# ScannerV2.net
KiCad netlist of a schematic drawn in Altium Designer
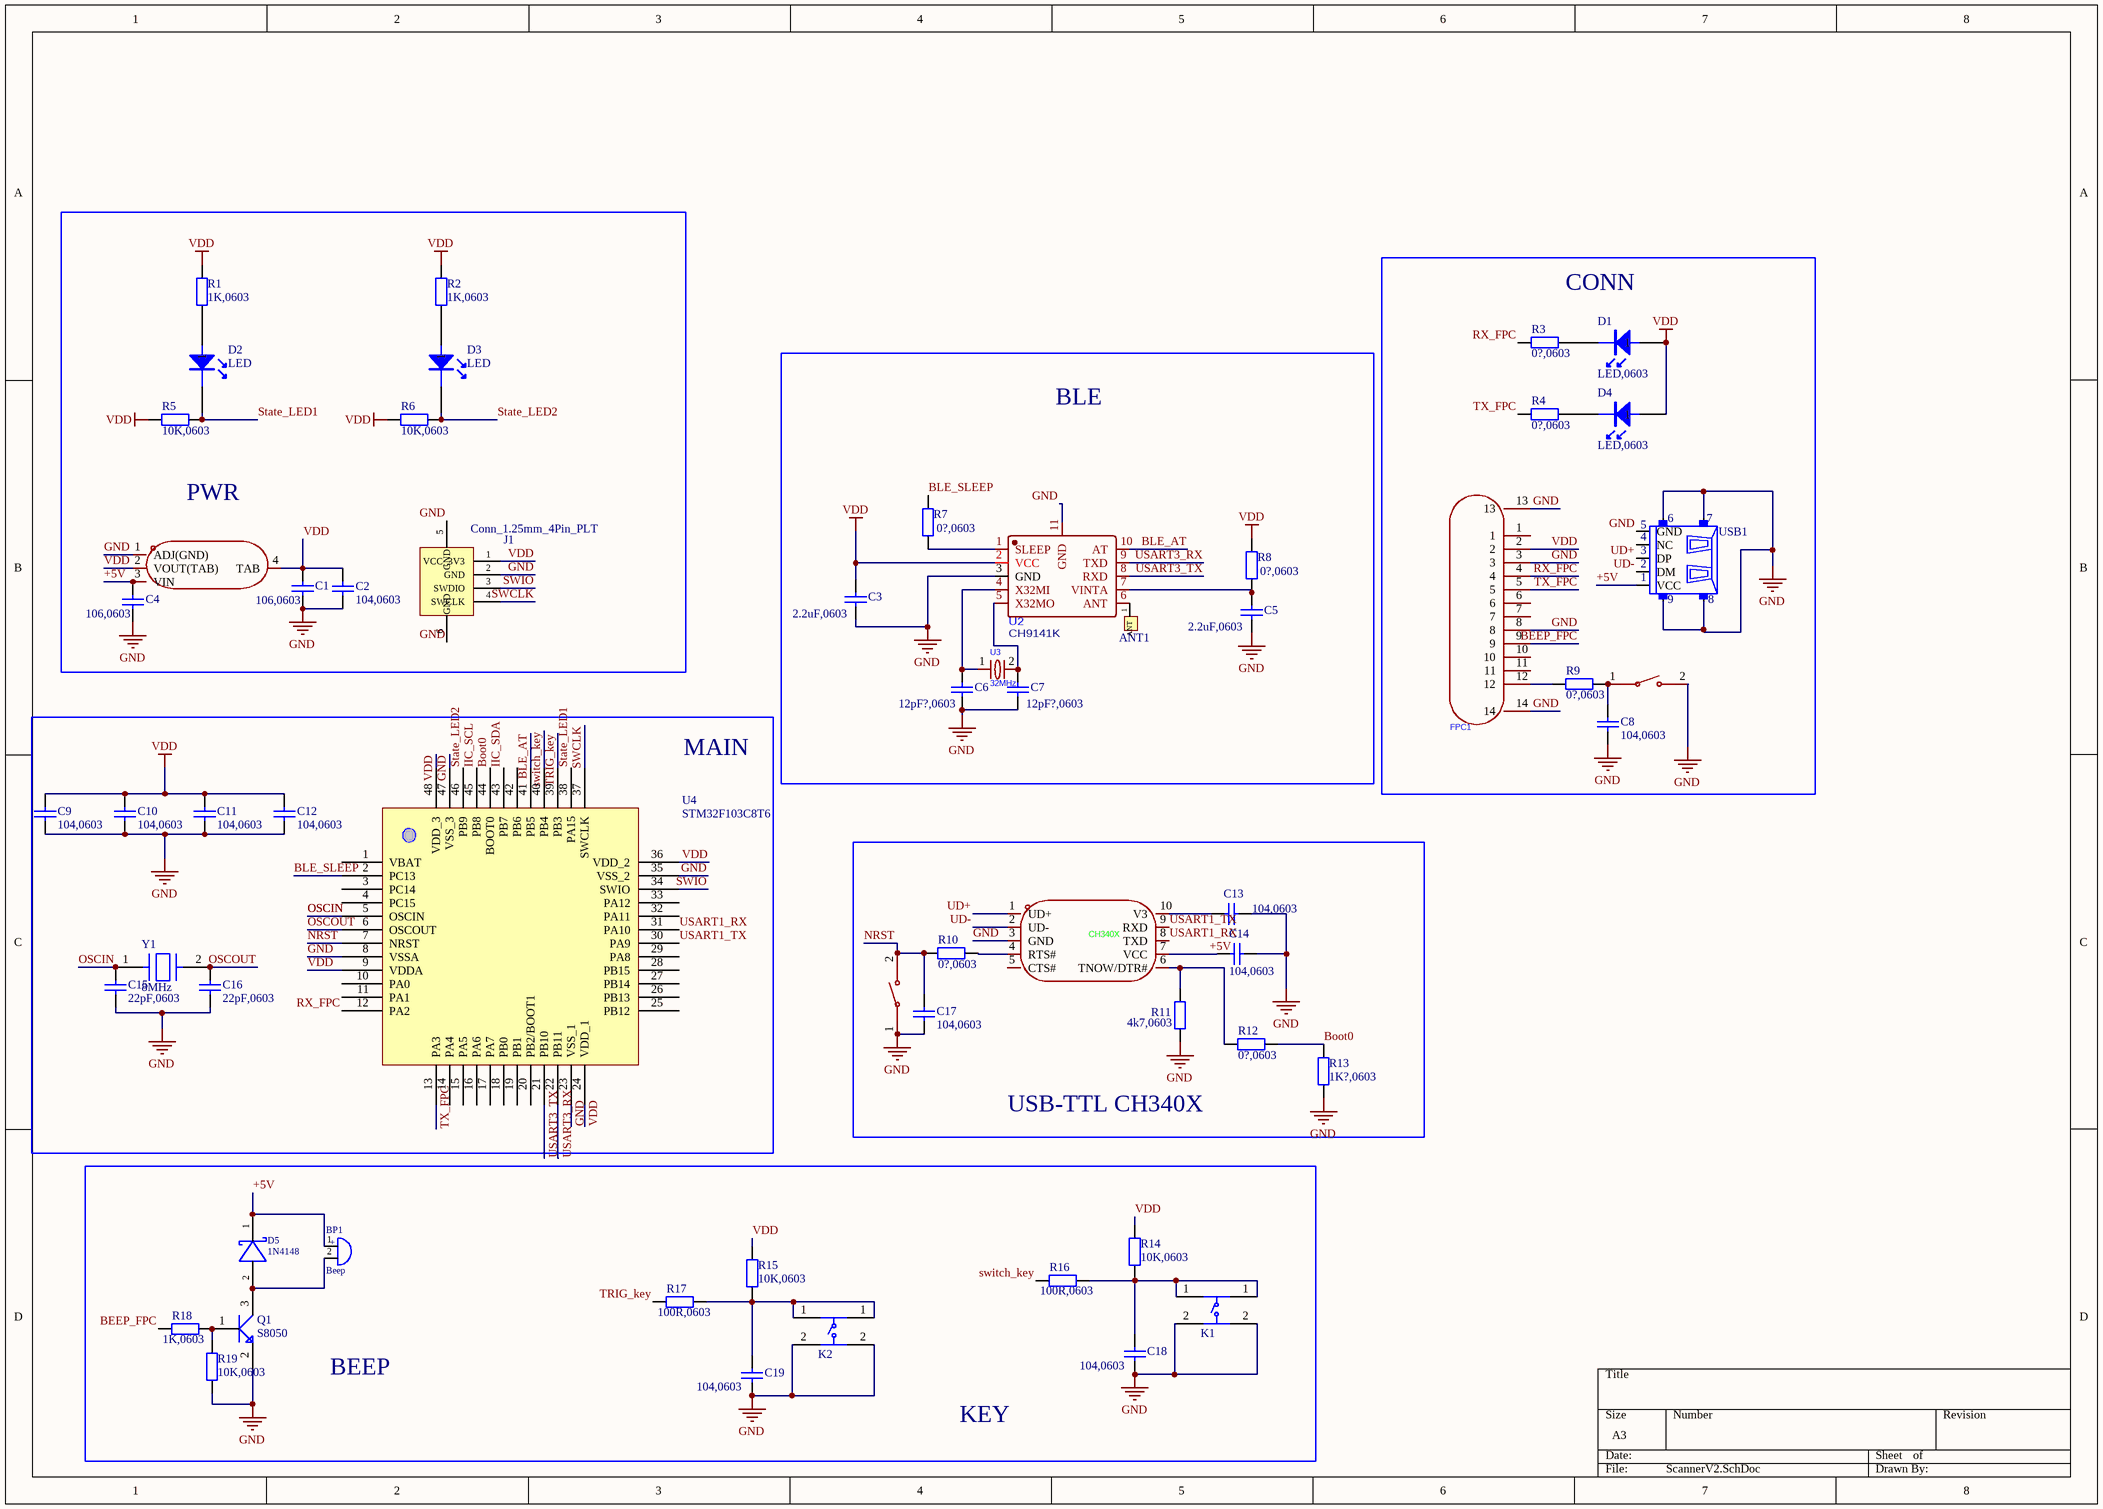
[diagram p0: ScannerV2.SchDoc]

(export (version "E")
  (design (tool "Eeschema 10.0.6"))
  (components
    (comp (ref "ANT1") (value "ANT") (footprint "IPX-2.0") (libsource (lib "HyperSTD") (part "ANT_IPX")))
    (comp (ref "BP1") (value "Beep") (footprint "BEEP") (libsource (lib "MQTT_SelService_V1") (part "Beep")))
    (comp (ref "C1")
      (value "106,0603")
      (footprint "C0603")
      (description "105,0603")
      (fields (field (name "PUBLISHER") "Altium Limited"))
      (libsource (lib "MQTT_SelService_V1") (part "Cap2"))
    )
    (comp (ref "C2")
      (value "104,0603")
      (footprint "C0603")
      (description "105,0603")
      (fields (field (name "PUBLISHER") "Altium Limited"))
      (libsource (lib "MQTT_SelService_V1") (part "Cap2"))
    )
    (comp (ref "C3")
      (value "2.2uF,0603")
      (footprint "C0603")
      (description "105,0603")
      (fields (field (name "PUBLISHER") "Altium Limited"))
      (libsource (lib "MQTT_SelService_V1") (part "Cap2"))
    )
    (comp (ref "C4")
      (value "106,0603")
      (footprint "C0603")
      (description "105,0603")
      (fields (field (name "PUBLISHER") "Altium Limited"))
      (libsource (lib "MQTT_SelService_V1") (part "Cap2"))
    )
    (comp (ref "C5")
      (value "2.2uF,0603")
      (footprint "C0603")
      (description "105,0603")
      (fields (field (name "PUBLISHER") "Altium Limited"))
      (libsource (lib "MQTT_SelService_V1") (part "Cap2"))
    )
    (comp (ref "C6")
      (value "12pF?,0603")
      (footprint "C0603")
      (description "105,0603")
      (fields (field (name "PUBLISHER") "Altium Limited"))
      (libsource (lib "MQTT_SelService_V1") (part "Cap2"))
    )
    (comp (ref "C7")
      (value "12pF?,0603")
      (footprint "C0603")
      (description "105,0603")
      (fields (field (name "PUBLISHER") "Altium Limited"))
      (libsource (lib "MQTT_SelService_V1") (part "Cap2"))
    )
    (comp (ref "C8")
      (value "104,0603")
      (footprint "C0603")
      (description "105,0603")
      (fields (field (name "PUBLISHER") "Altium Limited"))
      (libsource (lib "MQTT_SelService_V1") (part "Cap2"))
    )
    (comp (ref "C9")
      (value "104,0603")
      (footprint "C0603")
      (description "105,0603")
      (fields (field (name "PUBLISHER") "Altium Limited"))
      (libsource (lib "MQTT_SelService_V1") (part "Cap2"))
    )
    (comp (ref "C10")
      (value "104,0603")
      (footprint "C0603")
      (description "105,0603")
      (fields (field (name "PUBLISHER") "Altium Limited"))
      (libsource (lib "MQTT_SelService_V1") (part "Cap2"))
    )
    (comp (ref "C11")
      (value "104,0603")
      (footprint "C0603")
      (description "105,0603")
      (fields (field (name "PUBLISHER") "Altium Limited"))
      (libsource (lib "MQTT_SelService_V1") (part "Cap2"))
    )
    (comp (ref "C12")
      (value "104,0603")
      (footprint "C0603")
      (description "105,0603")
      (fields (field (name "PUBLISHER") "Altium Limited"))
      (libsource (lib "MQTT_SelService_V1") (part "Cap2"))
    )
    (comp (ref "C13")
      (value "104,0603")
      (footprint "C0603")
      (description "105,0603")
      (fields (field (name "PUBLISHER") "Altium Limited"))
      (libsource (lib "MQTT_SelService_V1") (part "Cap2"))
    )
    (comp (ref "C14")
      (value "104,0603")
      (footprint "C0603")
      (description "105,0603")
      (fields (field (name "PUBLISHER") "Altium Limited"))
      (libsource (lib "MQTT_SelService_V1") (part "Cap2"))
    )
    (comp (ref "C15")
      (value "22pF,0603")
      (footprint "C0603")
      (description "105,0603")
      (fields (field (name "PUBLISHER") "Altium Limited"))
      (libsource (lib "MQTT_SelService_V1") (part "Cap2"))
    )
    (comp (ref "C16")
      (value "22pF,0603")
      (footprint "C0603")
      (description "105,0603")
      (fields (field (name "PUBLISHER") "Altium Limited"))
      (libsource (lib "MQTT_SelService_V1") (part "Cap2"))
    )
    (comp (ref "C17")
      (value "104,0603")
      (footprint "C0603")
      (description "105,0603")
      (fields (field (name "PUBLISHER") "Altium Limited"))
      (libsource (lib "MQTT_SelService_V1") (part "Cap2"))
    )
    (comp (ref "C18")
      (value "104,0603")
      (footprint "C0603")
      (description "105,0603")
      (fields (field (name "PUBLISHER") "Altium Limited"))
      (libsource (lib "MQTT_SelService_V1") (part "Cap2"))
    )
    (comp (ref "C19")
      (value "104,0603")
      (footprint "C0603")
      (description "105,0603")
      (fields (field (name "PUBLISHER") "Altium Limited"))
      (libsource (lib "MQTT_SelService_V1") (part "Cap2"))
    )
    (comp (ref "D1")
      (value "LED,0603")
      (footprint "LED0603")
      (libsource (lib "MQTT_SelService_V1") (part "LED0603"))
    )
    (comp (ref "D2")
      (value "LED")
      (footprint "LED-2.5mm")
      (libsource (lib "MQTT_SelService_V1") (part "LED"))
    )
    (comp (ref "D3")
      (value "LED")
      (footprint "LED-2.5mm")
      (libsource (lib "MQTT_SelService_V1") (part "LED"))
    )
    (comp (ref "D4")
      (value "LED,0603")
      (footprint "LED0603")
      (libsource (lib "MQTT_SelService_V1") (part "LED0603"))
    )
    (comp (ref "D5")
      (value "1N4148")
      (footprint "1N4148")
      (description "SOD-123")
      (libsource (lib "MQTT_SelService_V1") (part "1N4148"))
    )
    (comp (ref "FPC1")
      (value "AFC01-S12FCA-00")
      (footprint "CONN-SMD-12P_AFC11-S12ICA-00")
      (fields (field (name "MANUFACTURER") "JS(钜硕电子)"))
      (libsource (lib "MQTT_SelService_V1") (part "FPC-12Pin_0.5"))
    )
    (comp (ref "J1")
      (value "Conn_1.25mm_4Pin_PLT")
      (footprint "CONN-SMD_4P-P1.25_HCTL_HC-1.25-4PLT")
      (description "SWD_Conn")
      (libsource (lib "MQTT_SelService_V1") (part "Conn_1.25mm_4Pin_PLT"))
    )
    (comp (ref "K1")
      (value "TS665CJ")
      (footprint "KEY12*12")
      (description "矩阵按键")
      (libsource (lib "MQTT_SelService_V1") (part "TS665CJ"))
    )
    (comp (ref "K2")
      (value "TS665CJ")
      (footprint "KEY12*12")
      (description "矩阵按键")
      (libsource (lib "MQTT_SelService_V1") (part "TS665CJ"))
    )
    (comp (ref "Q1")
      (value "S8050")
      (footprint "S8050")
      (libsource (lib "MQTT_SelService_V1") (part "S8050"))
    )
    (comp (ref "R1")
      (value "1K,0603")
      (footprint "R0603")
      (description "0603")
      (fields (field (name "PUBLISHER") "Altium Limited"))
      (libsource (lib "") (part "Res2_1"))
    )
    (comp (ref "R2")
      (value "1K,0603")
      (footprint "R0603")
      (description "0603")
      (fields (field (name "PUBLISHER") "Altium Limited"))
      (libsource (lib "") (part "Res2_1"))
    )
    (comp (ref "R3")
      (value "0?,0603")
      (footprint "R0603")
      (description "0603")
      (fields (field (name "PUBLISHER") "Altium Limited"))
      (libsource (lib "MQTT_SelService_V1") (part "Res2"))
    )
    (comp (ref "R4")
      (value "0?,0603")
      (footprint "R0603")
      (description "0603")
      (fields (field (name "PUBLISHER") "Altium Limited"))
      (libsource (lib "MQTT_SelService_V1") (part "Res2"))
    )
    (comp (ref "R5")
      (value "10K,0603")
      (footprint "R0603")
      (description "0603")
      (fields (field (name "PUBLISHER") "Altium Limited"))
      (libsource (lib "MQTT_SelService_V1") (part "Res2"))
    )
    (comp (ref "R6")
      (value "10K,0603")
      (footprint "R0603")
      (description "0603")
      (fields (field (name "PUBLISHER") "Altium Limited"))
      (libsource (lib "MQTT_SelService_V1") (part "Res2"))
    )
    (comp (ref "R7")
      (value "0?,0603")
      (footprint "R0603")
      (description "0603")
      (fields (field (name "PUBLISHER") "Altium Limited"))
      (libsource (lib "") (part "Res2_1"))
    )
    (comp (ref "R8")
      (value "0?,0603")
      (footprint "R0603")
      (description "0603")
      (fields (field (name "PUBLISHER") "Altium Limited"))
      (libsource (lib "") (part "Res2_1"))
    )
    (comp (ref "R9")
      (value "0?,0603")
      (footprint "R0603")
      (description "0603")
      (fields (field (name "PUBLISHER") "Altium Limited"))
      (libsource (lib "MQTT_SelService_V1") (part "Res2"))
    )
    (comp (ref "R10")
      (value "0?,0603")
      (footprint "R0603")
      (description "0603")
      (fields (field (name "PUBLISHER") "Altium Limited"))
      (libsource (lib "MQTT_SelService_V1") (part "Res2"))
    )
    (comp (ref "R11")
      (value "4k7,0603")
      (footprint "R0603")
      (description "0603")
      (fields (field (name "PUBLISHER") "Altium Limited"))
      (libsource (lib "") (part "Res2_3"))
    )
    (comp (ref "R12")
      (value "0?,0603")
      (footprint "R0603")
      (description "0603")
      (fields (field (name "PUBLISHER") "Altium Limited"))
      (libsource (lib "MQTT_SelService_V1") (part "Res2"))
    )
    (comp (ref "R13")
      (value "1K?,0603")
      (footprint "R0603")
      (description "0603")
      (fields (field (name "PUBLISHER") "Altium Limited"))
      (libsource (lib "") (part "Res2_3"))
    )
    (comp (ref "R14")
      (value "10K,0603")
      (footprint "R0603")
      (description "0603")
      (fields (field (name "PUBLISHER") "Altium Limited"))
      (libsource (lib "") (part "Res2_1"))
    )
    (comp (ref "R15")
      (value "10K,0603")
      (footprint "R0603")
      (description "0603")
      (fields (field (name "PUBLISHER") "Altium Limited"))
      (libsource (lib "") (part "Res2_1"))
    )
    (comp (ref "R16")
      (value "100R,0603")
      (footprint "R0603")
      (description "0603")
      (fields (field (name "PUBLISHER") "Altium Limited"))
      (libsource (lib "") (part "Res2_2"))
    )
    (comp (ref "R17")
      (value "100R,0603")
      (footprint "R0603")
      (description "0603")
      (fields (field (name "PUBLISHER") "Altium Limited"))
      (libsource (lib "") (part "Res2_2"))
    )
    (comp (ref "R18")
      (value "1K,0603")
      (footprint "R0603")
      (description "0603")
      (fields (field (name "PUBLISHER") "Altium Limited"))
      (libsource (lib "") (part "Res2_2"))
    )
    (comp (ref "R19")
      (value "10K,0603")
      (footprint "R0603")
      (description "0603")
      (fields (field (name "PUBLISHER") "Altium Limited"))
      (libsource (lib "") (part "Res2_3"))
    )
    (comp (ref "SW1")
      (value "K2-1107ST-A4DW-06")
      (footprint "KEY-SMD_L6.2-W3.6-LS8.0")
      (fields (field (name "MANUFACTURER") "韩国韩荣"))
      (libsource (lib "MQTT_SelService_V1") (part "K2-1107ST-A4DW-06"))
    )
    (comp (ref "SW2")
      (value "K2-1107ST-A4DW-06")
      (footprint "KEY-SMD_L6.2-W3.6-LS8.0")
      (fields (field (name "MANUFACTURER") "韩国韩荣"))
      (libsource (lib "MQTT_SelService_V1") (part "K2-1107ST-A4DW-06"))
    )
    (comp (ref "U1")
      (value "AMS1117-3.3")
      (footprint "SOT-223-4_L6.5-W3.5-P2.30-LS7.0-BR")
      (fields (field (name "MANUFACTURER") "UMW(友台半导体)"))
      (libsource (lib "HyperSTD") (part "AMS1117-3.3_C347222"))
    )
    (comp (ref "U2")
      (value "CH9141K")
      (footprint "CH9141K")
      (libsource (lib "MQTT_SelService_V1") (part "CH9141K"))
    )
    (comp (ref "U3")
      (value "32MHz")
      (footprint "32MHz_2016")
      (fields
        (field (name "MANUFACTURER") "HCI(杭晶)")
        (field (name "MANUFACTURER PART") "FL26T2-32.000-NTLLLDTL")
      )
      (libsource (lib "MQTT_SelService_V1") (part "32kHz"))
    )
    (comp (ref "U4")
      (value "STM32F103C8T6")
      (footprint "LQFP-48_L7.0-W7.0-P0.50-LS9.0-BL")
      (libsource (lib "MQTT_SelService_V1") (part "STM32F103C8T6"))
    )
    (comp (ref "U5")
      (value "CH340X")
      (footprint "CH340X")
      (fields (field (name "MANUFACTURER") "WCH(南京沁恒)"))
      (libsource (lib "MQTT_SelService_V1") (part "CH340X"))
    )
    (comp (ref "USB1")
      (value "USB-5PIN")
      (footprint "MICRO-USB-SMD_MICROXNJ")
      (description "with_PWR")
      (libsource (lib "MQTT_SelService_V1") (part "USB-5PIN_PWR"))
    )
    (comp (ref "Y1") (value "8MHz") (footprint "8MHz") (libsource (lib "MQTT_SelService_V1") (part "8MHz")))
  )
  (nets
    (net (code "1") (name "/+5V") (class "Default")
      (node (ref "BP1") (pin "1") (pinfunction "1_1") (pintype "passive"))
      (node (ref "C14") (pin "1") (pinfunction "1_1") (pintype "passive"))
      (node (ref "C4") (pin "2") (pinfunction "2_2") (pintype "passive"))
      (node (ref "D5") (pin "1") (pinfunction "1_1") (pintype "passive"))
      (node (ref "U1") (pin "3") (pinfunction "VIN_3") (pintype "passive"))
      (node (ref "U5") (pin "7") (pinfunction "VCC_7") (pintype "passive"))
      (node (ref "USB1") (pin "1") (pinfunction "VCC_1") (pintype "passive"))
    )
    (net (code "2") (name "/BEEP_FPC") (class "Default")
      (node (ref "FPC1") (pin "9") (pinfunction "9_9") (pintype "passive"))
      (node (ref "R18") (pin "1") (pinfunction "1_1") (pintype "passive"))
    )
    (net (code "3") (name "/BLE_AT") (class "Default")
      (node (ref "U2") (pin "10") (pinfunction "AT_10") (pintype "passive"))
      (node (ref "U4") (pin "41") (pinfunction "PB5_41") (pintype "passive"))
    )
    (net (code "4") (name "/BLE_SLEEP") (class "Default")
      (node (ref "R7") (pin "2") (pinfunction "2_2") (pintype "passive"))
      (node (ref "U4") (pin "2") (pinfunction "PC13_2") (pintype "passive"))
    )
    (net (code "5") (name "/Boot0") (class "Default")
      (node (ref "R12") (pin "1") (pinfunction "1_1") (pintype "passive"))
      (node (ref "R13") (pin "1") (pinfunction "1_1") (pintype "passive"))
      (node (ref "U4") (pin "44") (pinfunction "BOOT0_44") (pintype "passive"))
    )
    (net (code "6") (name "/IIC_SCL") (class "Default")
      (node (ref "U4") (pin "45") (pinfunction "PB8_45") (pintype "passive"))
    )
    (net (code "7") (name "/IIC_SDA") (class "Default")
      (node (ref "U4") (pin "43") (pinfunction "PB7_43") (pintype "passive"))
    )
    (net (code "8") (name "/NRST") (class "Default")
      (node (ref "C17") (pin "1") (pinfunction "1_1") (pintype "passive"))
      (node (ref "R10") (pin "2") (pinfunction "2_2") (pintype "passive"))
      (node (ref "SW2") (pin "2") (pinfunction "2_2") (pintype "passive"))
      (node (ref "U4") (pin "7") (pinfunction "NRST_7") (pintype "passive"))
    )
    (net (code "9") (name "/OSCIN") (class "Default")
      (node (ref "C15") (pin "2") (pinfunction "2_2") (pintype "passive"))
      (node (ref "U4") (pin "5") (pinfunction "OSCIN_5") (pintype "passive"))
      (node (ref "Y1") (pin "1") (pinfunction "1_1") (pintype "passive"))
    )
    (net (code "10") (name "/OSCOUT") (class "Default")
      (node (ref "C16") (pin "2") (pinfunction "2_2") (pintype "passive"))
      (node (ref "U4") (pin "6") (pinfunction "OSCOUT_6") (pintype "passive"))
      (node (ref "Y1") (pin "2") (pinfunction "2_2") (pintype "passive"))
    )
    (net (code "11") (name "/RX_FPC") (class "Default")
      (node (ref "FPC1") (pin "4") (pinfunction "4_4") (pintype "passive"))
      (node (ref "R3") (pin "2") (pinfunction "2_2") (pintype "passive"))
      (node (ref "U4") (pin "12") (pinfunction "PA2_12") (pintype "passive"))
    )
    (net (code "12") (name "/SWCLK") (class "Default")
      (node (ref "J1") (pin "4") (pinfunction "SWCLK_4") (pintype "passive"))
      (node (ref "U4") (pin "37") (pinfunction "SWCLK_37") (pintype "passive"))
    )
    (net (code "13") (name "/SWIO") (class "Default")
      (node (ref "J1") (pin "3") (pinfunction "SWDIO_3") (pintype "passive"))
      (node (ref "U4") (pin "34") (pinfunction "SWIO_34") (pintype "passive"))
    )
    (net (code "14") (name "/State_LED1") (class "Default")
      (node (ref "D2") (pin "2") (pinfunction "2_2") (pintype "passive"))
      (node (ref "R5") (pin "1") (pinfunction "1_1") (pintype "passive"))
      (node (ref "U4") (pin "38") (pinfunction "PA15_38") (pintype "passive"))
    )
    (net (code "15") (name "/State_LED2") (class "Default")
      (node (ref "D3") (pin "2") (pinfunction "2_2") (pintype "passive"))
      (node (ref "R6") (pin "1") (pinfunction "1_1") (pintype "passive"))
      (node (ref "U4") (pin "46") (pinfunction "PB9_46") (pintype "passive"))
    )
    (net (code "16") (name "/TRIG_key") (class "Default")
      (node (ref "R17") (pin "1") (pinfunction "1_1") (pintype "passive"))
      (node (ref "U4") (pin "39") (pinfunction "PB3_39") (pintype "passive"))
    )
    (net (code "17") (name "/TX_FPC") (class "Default")
      (node (ref "FPC1") (pin "5") (pinfunction "5_5") (pintype "passive"))
      (node (ref "R4") (pin "2") (pinfunction "2_2") (pintype "passive"))
      (node (ref "U4") (pin "13") (pinfunction "PA3_13") (pintype "passive"))
    )
    (net (code "18") (name "/UD+") (class "Default")
      (node (ref "U5") (pin "1") (pinfunction "UD+_1") (pintype "passive"))
      (node (ref "USB1") (pin "3") (pinfunction "DP_3") (pintype "passive"))
    )
    (net (code "19") (name "/UD-") (class "Default")
      (node (ref "U5") (pin "2") (pinfunction "UD-_2") (pintype "passive"))
      (node (ref "USB1") (pin "2") (pinfunction "DM_2") (pintype "passive"))
    )
    (net (code "20") (name "/USART1_RX") (class "Default")
      (node (ref "U4") (pin "31") (pinfunction "PA10_31") (pintype "passive"))
      (node (ref "U5") (pin "8") (pinfunction "TXD_8") (pintype "passive"))
    )
    (net (code "21") (name "/USART1_TX") (class "Default")
      (node (ref "U4") (pin "30") (pinfunction "PA9_30") (pintype "passive"))
      (node (ref "U5") (pin "9") (pinfunction "RXD_9") (pintype "passive"))
    )
    (net (code "22") (name "/USART3_RX") (class "Default")
      (node (ref "U2") (pin "9") (pinfunction "TXD_9") (pintype "passive"))
      (node (ref "U4") (pin "22") (pinfunction "PB11_22") (pintype "passive"))
    )
    (net (code "23") (name "/USART3_TX") (class "Default")
      (node (ref "U2") (pin "8") (pinfunction "RXD_8") (pintype "passive"))
      (node (ref "U4") (pin "21") (pinfunction "PB10_21") (pintype "passive"))
    )
    (net (code "24") (name "/switch_key") (class "Default")
      (node (ref "R16") (pin "1") (pinfunction "1_1") (pintype "passive"))
      (node (ref "U4") (pin "40") (pinfunction "PB4_40") (pintype "passive"))
    )
    (net (code "25") (name "GND") (class "Default")
      (node (ref "C1") (pin "1") (pinfunction "1_1") (pintype "passive"))
      (node (ref "C10") (pin "1") (pinfunction "1_1") (pintype "passive"))
      (node (ref "C11") (pin "1") (pinfunction "1_1") (pintype "passive"))
      (node (ref "C12") (pin "1") (pinfunction "1_1") (pintype "passive"))
      (node (ref "C13") (pin "2") (pinfunction "2_2") (pintype "passive"))
      (node (ref "C14") (pin "2") (pinfunction "2_2") (pintype "passive"))
      (node (ref "C15") (pin "1") (pinfunction "1_1") (pintype "passive"))
      (node (ref "C16") (pin "1") (pinfunction "1_1") (pintype "passive"))
      (node (ref "C17") (pin "2") (pinfunction "2_2") (pintype "passive"))
      (node (ref "C18") (pin "1") (pinfunction "1_1") (pintype "passive"))
      (node (ref "C19") (pin "1") (pinfunction "1_1") (pintype "passive"))
      (node (ref "C2") (pin "1") (pinfunction "1_1") (pintype "passive"))
      (node (ref "C3") (pin "2") (pinfunction "2_2") (pintype "passive"))
      (node (ref "C4") (pin "1") (pinfunction "1_1") (pintype "passive"))
      (node (ref "C5") (pin "2") (pinfunction "2_2") (pintype "passive"))
      (node (ref "C6") (pin "2") (pinfunction "2_2") (pintype "passive"))
      (node (ref "C7") (pin "2") (pinfunction "2_2") (pintype "passive"))
      (node (ref "C8") (pin "1") (pinfunction "1_1") (pintype "passive"))
      (node (ref "C9") (pin "1") (pinfunction "1_1") (pintype "passive"))
      (node (ref "FPC1") (pin "13") (pinfunction "13_13") (pintype "passive"))
      (node (ref "FPC1") (pin "14") (pinfunction "14_14") (pintype "passive"))
      (node (ref "FPC1") (pin "3") (pinfunction "3_3") (pintype "passive"))
      (node (ref "FPC1") (pin "8") (pinfunction "8_8") (pintype "passive"))
      (node (ref "J1") (pin "2") (pinfunction "GND_2") (pintype "passive"))
      (node (ref "J1") (pin "5") (pinfunction "GND_5") (pintype "passive"))
      (node (ref "J1") (pin "6") (pinfunction "GND_6") (pintype "passive"))
      (node (ref "K1") (pin "2") (pinfunction "2_2") (pintype "passive"))
      (node (ref "K2") (pin "2") (pinfunction "2_2") (pintype "passive"))
      (node (ref "Q1") (pin "2") (pinfunction "2_2") (pintype "passive"))
      (node (ref "R11") (pin "2") (pinfunction "2_2") (pintype "passive"))
      (node (ref "R13") (pin "2") (pinfunction "2_2") (pintype "passive"))
      (node (ref "R19") (pin "2") (pinfunction "2_2") (pintype "passive"))
      (node (ref "SW1") (pin "2") (pinfunction "2_2") (pintype "passive"))
      (node (ref "SW2") (pin "1") (pinfunction "1_1") (pintype "passive"))
      (node (ref "U1") (pin "1") (pinfunction "ADJ(GND)_1") (pintype "passive"))
      (node (ref "U2") (pin "11") (pinfunction "GND_11") (pintype "passive"))
      (node (ref "U2") (pin "3") (pinfunction "GND_3") (pintype "passive"))
      (node (ref "U4") (pin "23") (pinfunction "VSS_1_23") (pintype "passive"))
      (node (ref "U4") (pin "35") (pinfunction "VSS_2_35") (pintype "passive"))
      (node (ref "U4") (pin "47") (pinfunction "VSS_3_47") (pintype "passive"))
      (node (ref "U4") (pin "8") (pinfunction "VSSA_8") (pintype "passive"))
      (node (ref "U5") (pin "3") (pinfunction "GND_3") (pintype "passive"))
      (node (ref "USB1") (pin "5") (pinfunction "GND_5") (pintype "passive"))
      (node (ref "USB1") (pin "6") (pinfunction "6_6") (pintype "passive"))
      (node (ref "USB1") (pin "7") (pinfunction "7_7") (pintype "passive"))
      (node (ref "USB1") (pin "8") (pinfunction "8_8") (pintype "passive"))
      (node (ref "USB1") (pin "9") (pinfunction "9_9") (pintype "passive"))
    )
    (net (code "26") (name "Net-(ANT1-ANT)") (class "Default")
      (node (ref "ANT1") (pin "1") (pinfunction "ANT_1") (pintype "passive"))
      (node (ref "U2") (pin "6") (pinfunction "ANT_6") (pintype "passive"))
    )
    (net (code "27") (name "Net-(BP1-Pad2)") (class "Default")
      (node (ref "BP1") (pin "2") (pinfunction "2_2") (pintype "passive"))
      (node (ref "D5") (pin "2") (pinfunction "2_2") (pintype "passive"))
      (node (ref "Q1") (pin "3") (pinfunction "3_3") (pintype "passive"))
    )
    (net (code "28") (name "Net-(C8-Pad2)") (class "Default")
      (node (ref "C8") (pin "2") (pinfunction "2_2") (pintype "passive"))
      (node (ref "R9") (pin "1") (pinfunction "1_1") (pintype "passive"))
      (node (ref "SW1") (pin "1") (pinfunction "1_1") (pintype "passive"))
    )
    (net (code "29") (name "Net-(C18-Pad2)") (class "Default")
      (node (ref "C18") (pin "2") (pinfunction "2_2") (pintype "passive"))
      (node (ref "K1") (pin "1") (pinfunction "1_1") (pintype "passive"))
      (node (ref "R14") (pin "1") (pinfunction "1_1") (pintype "passive"))
      (node (ref "R16") (pin "2") (pinfunction "2_2") (pintype "passive"))
    )
    (net (code "30") (name "Net-(C19-Pad2)") (class "Default")
      (node (ref "C19") (pin "2") (pinfunction "2_2") (pintype "passive"))
      (node (ref "K2") (pin "1") (pinfunction "1_1") (pintype "passive"))
      (node (ref "R15") (pin "1") (pinfunction "1_1") (pintype "passive"))
      (node (ref "R17") (pin "2") (pinfunction "2_2") (pintype "passive"))
    )
    (net (code "31") (name "Net-(D1-Pad2)") (class "Default")
      (node (ref "D1") (pin "2") (pinfunction "2_2") (pintype "passive"))
      (node (ref "R3") (pin "1") (pinfunction "1_1") (pintype "passive"))
    )
    (net (code "32") (name "Net-(D2-Pad1)") (class "Default")
      (node (ref "D2") (pin "1") (pinfunction "1_1") (pintype "passive"))
      (node (ref "R1") (pin "1") (pinfunction "1_1") (pintype "passive"))
    )
    (net (code "33") (name "Net-(D3-Pad1)") (class "Default")
      (node (ref "D3") (pin "1") (pinfunction "1_1") (pintype "passive"))
      (node (ref "R2") (pin "1") (pinfunction "1_1") (pintype "passive"))
    )
    (net (code "34") (name "Net-(D4-Pad2)") (class "Default")
      (node (ref "D4") (pin "2") (pinfunction "2_2") (pintype "passive"))
      (node (ref "R4") (pin "1") (pinfunction "1_1") (pintype "passive"))
    )
    (net (code "35") (name "Net-(FPC1-Pad12)") (class "Default")
      (node (ref "FPC1") (pin "12") (pinfunction "12_12") (pintype "passive"))
      (node (ref "R9") (pin "2") (pinfunction "2_2") (pintype "passive"))
    )
    (net (code "36") (name "Net-(Q1-Pad1)") (class "Default")
      (node (ref "Q1") (pin "1") (pinfunction "1_1") (pintype "passive"))
      (node (ref "R18") (pin "2") (pinfunction "2_2") (pintype "passive"))
      (node (ref "R19") (pin "1") (pinfunction "1_1") (pintype "passive"))
    )
    (net (code "37") (name "Net-(U2-SLEEP)") (class "Default")
      (node (ref "R7") (pin "1") (pinfunction "1_1") (pintype "passive"))
      (node (ref "U2") (pin "1") (pinfunction "SLEEP_1") (pintype "passive"))
    )
    (net (code "38") (name "Net-(U2-VINTA)") (class "Default")
      (node (ref "C5") (pin "1") (pinfunction "1_1") (pintype "passive"))
      (node (ref "R8") (pin "1") (pinfunction "1_1") (pintype "passive"))
      (node (ref "U2") (pin "7") (pinfunction "VINTA_7") (pintype "passive"))
    )
    (net (code "39") (name "Net-(U2-X32MI)") (class "Default")
      (node (ref "C6") (pin "1") (pinfunction "1_1") (pintype "passive"))
      (node (ref "U2") (pin "4") (pinfunction "X32MI_4") (pintype "passive"))
      (node (ref "U3") (pin "1") (pinfunction "1_1") (pintype "passive"))
    )
    (net (code "40") (name "Net-(U2-X32MO)") (class "Default")
      (node (ref "C7") (pin "1") (pinfunction "1_1") (pintype "passive"))
      (node (ref "U2") (pin "5") (pinfunction "X32MO_5") (pintype "passive"))
      (node (ref "U3") (pin "2") (pinfunction "GND_2") (pintype "passive"))
    )
    (net (code "41") (name "Net-(U5-RTS#)") (class "Default")
      (node (ref "R10") (pin "1") (pinfunction "1_1") (pintype "passive"))
      (node (ref "U5") (pin "4") (pinfunction "RTS#_4") (pintype "passive"))
    )
    (net (code "42") (name "Net-(U5-TNOW{slash}DTR#)") (class "Default")
      (node (ref "R11") (pin "1") (pinfunction "1_1") (pintype "passive"))
      (node (ref "R12") (pin "2") (pinfunction "2_2") (pintype "passive"))
      (node (ref "U5") (pin "6") (pinfunction "TNOW/DTR#_6") (pintype "passive"))
    )
    (net (code "43") (name "Net-(U5-V3)") (class "Default")
      (node (ref "C13") (pin "1") (pinfunction "1_1") (pintype "passive"))
      (node (ref "U5") (pin "10") (pinfunction "V3_10") (pintype "passive"))
    )
    (net (code "44") (name "VDD") (class "Default")
      (node (ref "C1") (pin "2") (pinfunction "2_2") (pintype "passive"))
      (node (ref "C10") (pin "2") (pinfunction "2_2") (pintype "passive"))
      (node (ref "C11") (pin "2") (pinfunction "2_2") (pintype "passive"))
      (node (ref "C12") (pin "2") (pinfunction "2_2") (pintype "passive"))
      (node (ref "C2") (pin "2") (pinfunction "2_2") (pintype "passive"))
      (node (ref "C3") (pin "1") (pinfunction "1_1") (pintype "passive"))
      (node (ref "C9") (pin "2") (pinfunction "2_2") (pintype "passive"))
      (node (ref "D1") (pin "1") (pinfunction "1_1") (pintype "passive"))
      (node (ref "D4") (pin "1") (pinfunction "1_1") (pintype "passive"))
      (node (ref "FPC1") (pin "2") (pinfunction "2_2") (pintype "passive"))
      (node (ref "J1") (pin "1") (pinfunction "VCC_3V3_1") (pintype "passive"))
      (node (ref "R1") (pin "2") (pinfunction "2_2") (pintype "passive"))
      (node (ref "R14") (pin "2") (pinfunction "2_2") (pintype "passive"))
      (node (ref "R15") (pin "2") (pinfunction "2_2") (pintype "passive"))
      (node (ref "R2") (pin "2") (pinfunction "2_2") (pintype "passive"))
      (node (ref "R5") (pin "2") (pinfunction "2_2") (pintype "passive"))
      (node (ref "R6") (pin "2") (pinfunction "2_2") (pintype "passive"))
      (node (ref "R8") (pin "2") (pinfunction "2_2") (pintype "passive"))
      (node (ref "U1") (pin "2") (pinfunction "VOUT(TAB)_2") (pintype "passive"))
      (node (ref "U1") (pin "4") (pinfunction "TAB_4") (pintype "passive"))
      (node (ref "U2") (pin "2") (pinfunction "VCC_2") (pintype "passive"))
      (node (ref "U4") (pin "24") (pinfunction "VDD_1_24") (pintype "passive"))
      (node (ref "U4") (pin "36") (pinfunction "VDD_2_36") (pintype "passive"))
      (node (ref "U4") (pin "48") (pinfunction "VDD_3_48") (pintype "passive"))
      (node (ref "U4") (pin "9") (pinfunction "VDDA_9") (pintype "passive"))
    )
    (net (code "45") (name "unconnected-(FPC1-Pad1)") (class "Default")
      (node (ref "FPC1") (pin "1") (pinfunction "1_1") (pintype "passive"))
    )
    (net (code "46") (name "unconnected-(FPC1-Pad6)") (class "Default")
      (node (ref "FPC1") (pin "6") (pinfunction "6_6") (pintype "passive"))
    )
    (net (code "47") (name "unconnected-(FPC1-Pad7)") (class "Default")
      (node (ref "FPC1") (pin "7") (pinfunction "7_7") (pintype "passive"))
    )
    (net (code "48") (name "unconnected-(FPC1-Pad10)") (class "Default")
      (node (ref "FPC1") (pin "10") (pinfunction "10_10") (pintype "passive"))
    )
    (net (code "49") (name "unconnected-(FPC1-Pad11)") (class "Default")
      (node (ref "FPC1") (pin "11") (pinfunction "11_11") (pintype "passive"))
    )
    (net (code "50") (name "unconnected-(U4-PA0-Pad10)") (class "Default")
      (node (ref "U4") (pin "10") (pinfunction "PA0_10") (pintype "passive"))
    )
    (net (code "51") (name "unconnected-(U4-PA1-Pad11)") (class "Default")
      (node (ref "U4") (pin "11") (pinfunction "PA1_11") (pintype "passive"))
    )
    (net (code "52") (name "unconnected-(U4-PA4-Pad14)") (class "Default")
      (node (ref "U4") (pin "14") (pinfunction "PA4_14") (pintype "passive"))
    )
    (net (code "53") (name "unconnected-(U4-PA5-Pad15)") (class "Default")
      (node (ref "U4") (pin "15") (pinfunction "PA5_15") (pintype "passive"))
    )
    (net (code "54") (name "unconnected-(U4-PA6-Pad16)") (class "Default")
      (node (ref "U4") (pin "16") (pinfunction "PA6_16") (pintype "passive"))
    )
    (net (code "55") (name "unconnected-(U4-PA7-Pad17)") (class "Default")
      (node (ref "U4") (pin "17") (pinfunction "PA7_17") (pintype "passive"))
    )
    (net (code "56") (name "unconnected-(U4-PA8-Pad29)") (class "Default")
      (node (ref "U4") (pin "29") (pinfunction "PA8_29") (pintype "passive"))
    )
    (net (code "57") (name "unconnected-(U4-PA11-Pad32)") (class "Default")
      (node (ref "U4") (pin "32") (pinfunction "PA11_32") (pintype "passive"))
    )
    (net (code "58") (name "unconnected-(U4-PA12-Pad33)") (class "Default")
      (node (ref "U4") (pin "33") (pinfunction "PA12_33") (pintype "passive"))
    )
    (net (code "59") (name "unconnected-(U4-PB0-Pad18)") (class "Default")
      (node (ref "U4") (pin "18") (pinfunction "PB0_18") (pintype "passive"))
    )
    (net (code "60") (name "unconnected-(U4-PB1-Pad19)") (class "Default")
      (node (ref "U4") (pin "19") (pinfunction "PB1_19") (pintype "passive"))
    )
    (net (code "61") (name "unconnected-(U4-PB2{slash}BOOT1-Pad20)") (class "Default")
      (node (ref "U4") (pin "20") (pinfunction "PB2/BOOT1_20") (pintype "passive"))
    )
    (net (code "62") (name "unconnected-(U4-PB6-Pad42)") (class "Default")
      (node (ref "U4") (pin "42") (pinfunction "PB6_42") (pintype "passive"))
    )
    (net (code "63") (name "unconnected-(U4-PB12-Pad25)") (class "Default")
      (node (ref "U4") (pin "25") (pinfunction "PB12_25") (pintype "passive"))
    )
    (net (code "64") (name "unconnected-(U4-PB13-Pad26)") (class "Default")
      (node (ref "U4") (pin "26") (pinfunction "PB13_26") (pintype "passive"))
    )
    (net (code "65") (name "unconnected-(U4-PB14-Pad27)") (class "Default")
      (node (ref "U4") (pin "27") (pinfunction "PB14_27") (pintype "passive"))
    )
    (net (code "66") (name "unconnected-(U4-PB15-Pad28)") (class "Default")
      (node (ref "U4") (pin "28") (pinfunction "PB15_28") (pintype "passive"))
    )
    (net (code "67") (name "unconnected-(U4-PC14-Pad3)") (class "Default")
      (node (ref "U4") (pin "3") (pinfunction "PC14_3") (pintype "passive"))
    )
    (net (code "68") (name "unconnected-(U4-PC15-Pad4)") (class "Default")
      (node (ref "U4") (pin "4") (pinfunction "PC15_4") (pintype "passive"))
    )
    (net (code "69") (name "unconnected-(U4-VBAT-Pad1)") (class "Default")
      (node (ref "U4") (pin "1") (pinfunction "VBAT_1") (pintype "passive"))
    )
    (net (code "70") (name "unconnected-(U5-CTS#-Pad5)") (class "Default")
      (node (ref "U5") (pin "5") (pinfunction "CTS#_5") (pintype "passive"))
    )
    (net (code "71") (name "unconnected-(USB1-NC-Pad4)") (class "Default")
      (node (ref "USB1") (pin "4") (pinfunction "NC_4") (pintype "passive"))
    )
  )
)
